# Power.net
KiCad netlist of a schematic drawn in Altium Designer
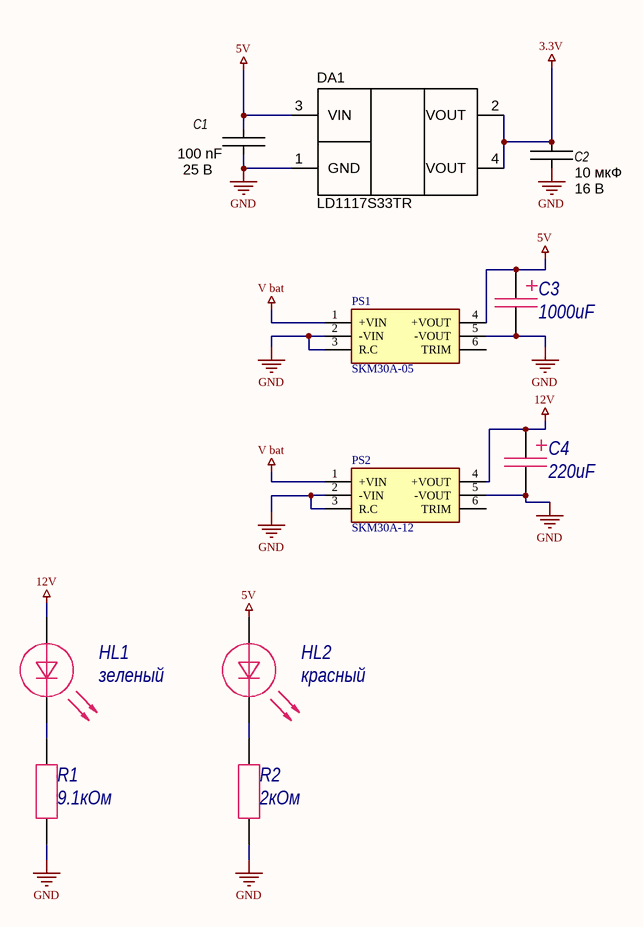
[diagram p0: Power.SchDoc]

(export (version "E")
  (design (tool "Eeschema 10.0.6"))
  (components
    (comp (ref "C1")
      (value "100 nF")
      (footprint "C0402C")
      (description "SMD 0603 ; X7R; 0,01 мкФ; 25 В")
      (fields
        (field (name "PART NUMBER") "CL05B103KA5NNNC")
        (field (name "MANUFACTURER") "SAMSUNG")
        (field (name "VOLTAGE") "25 В")
      )
      (libsource (lib "Capacitors") (part "CL05B103KA5NNNC"))
    )
    (comp (ref "C2")
      (value "10 мкФ")
      (footprint "C0805C")
      (description "SMD 0805; X7R; 10 мкФ; 16 В")
      (fields
        (field (name "PART NUMBER") "CL21B106KOQNNNE")
        (field (name "MANUFACTURER") "SAMSUNG")
        (field (name "VOLTAGE") "16 В")
      )
      (libsource (lib "Capacitors") (part "CL21B106KOQNNNE"))
    )
    (comp (ref "C3")
      (value "1000uF")
      (footprint "Capacitor 8x12")
      (fields (field (name "Comment") "1uF"))
      (libsource (lib "Hydrolib_sch") (part "Capacitor_pol"))
    )
    (comp (ref "C4")
      (value "220uF")
      (footprint "Capacitor 8x12")
      (fields (field (name "Comment") "1uF"))
      (libsource (lib "Hydrolib_sch") (part "Capacitor_pol"))
    )
    (comp (ref "DA1")
      (value "LD1117S33TR")
      (footprint "SOT-223")
      (description "Linear regulator, 3V3")
      (fields (field (name "MANUFACTURER") "STMicroelectronics") (field (name "PART NUMBER") "LD1117S33TR"))
      (libsource (lib "IC") (part "LD1117S33TR"))
    )
    (comp (ref "HL1")
      (value "~")
      (footprint "0805D")
      (fields (field (name "COLOR") "зеленый"))
      (libsource (lib "Hydrolib_sch") (part "LED"))
    )
    (comp (ref "HL2")
      (value "~")
      (footprint "0805D")
      (fields (field (name "COLOR") "красный"))
      (libsource (lib "Hydrolib_sch") (part "LED"))
    )
    (comp (ref "PS1")
      (value "SKM30A-05")
      (footprint "SKM30A05")
      (description "Power Supply")
      (fields (field (name "MOUSER PART NUMBER") "709-SKM30A-05"))
      (libsource (lib "SamacSys") (part "SKM30A-05"))
    )
    (comp (ref "PS2")
      (value "SKM30A-12")
      (footprint "SKM30B12")
      (description "Power Supply")
      (fields (field (name "MOUSER PART NUMBER") "709-SKM30A-12"))
      (libsource (lib "SamacSys") (part "SKM30A-12"))
    )
    (comp (ref "R1")
      (value "9.1кОм")
      (footprint "0805R")
      (fields (field (name "Comment") "Resistor"))
      (libsource (lib "Hydrolib_sch") (part "Resistor"))
    )
    (comp (ref "R2")
      (value "2кОм")
      (footprint "0805R")
      (fields (field (name "Comment") "Resistor"))
      (libsource (lib "Hydrolib_sch") (part "Resistor"))
    )
  )
  (nets
    (net (code "1") (name "3.3V") (class "Default")
      (node (ref "C2") (pin "1") (pinfunction "1_1") (pintype "passive"))
      (node (ref "DA1") (pin "2") (pinfunction "VOUT_2") (pintype "passive"))
      (node (ref "DA1") (pin "4") (pinfunction "VOUT_4") (pintype "passive"))
    )
    (net (code "2") (name "5V") (class "Default")
      (node (ref "C1") (pin "1") (pinfunction "1_1") (pintype "passive"))
      (node (ref "C3") (pin "1") (pinfunction "1_1") (pintype "passive"))
      (node (ref "DA1") (pin "3") (pinfunction "VIN_3") (pintype "passive"))
      (node (ref "HL2") (pin "1") (pinfunction "1_1") (pintype "passive"))
      (node (ref "PS1") (pin "4") (pinfunction "+VOUT_4") (pintype "passive"))
    )
    (net (code "3") (name "12V") (class "Default")
      (node (ref "C4") (pin "1") (pinfunction "1_1") (pintype "passive"))
      (node (ref "HL1") (pin "1") (pinfunction "1_1") (pintype "passive"))
      (node (ref "PS2") (pin "4") (pinfunction "+VOUT_4") (pintype "passive"))
    )
    (net (code "4") (name "GND") (class "Default")
      (node (ref "C1") (pin "2") (pinfunction "2_2") (pintype "passive"))
      (node (ref "C2") (pin "2") (pinfunction "2_2") (pintype "passive"))
      (node (ref "C3") (pin "2") (pinfunction "2_2") (pintype "passive"))
      (node (ref "C4") (pin "2") (pinfunction "2_2") (pintype "passive"))
      (node (ref "DA1") (pin "1") (pinfunction "GND_1") (pintype "passive"))
      (node (ref "PS1") (pin "2") (pinfunction "-VIN_2") (pintype "passive"))
      (node (ref "PS1") (pin "3") (pinfunction "R.C_3") (pintype "passive"))
      (node (ref "PS1") (pin "5") (pinfunction "-VOUT_5") (pintype "passive"))
      (node (ref "PS2") (pin "2") (pinfunction "-VIN_2") (pintype "passive"))
      (node (ref "PS2") (pin "3") (pinfunction "R.C_3") (pintype "passive"))
      (node (ref "PS2") (pin "5") (pinfunction "-VOUT_5") (pintype "passive"))
      (node (ref "R1") (pin "1") (pinfunction "1_1") (pintype "passive"))
      (node (ref "R2") (pin "1") (pinfunction "1_1") (pintype "passive"))
    )
    (net (code "5") (name "Net-(HL1-Pad2)") (class "Default")
      (node (ref "HL1") (pin "2") (pinfunction "2_2") (pintype "passive"))
      (node (ref "R1") (pin "2") (pinfunction "2_2") (pintype "passive"))
    )
    (net (code "6") (name "Net-(HL2-Pad2)") (class "Default")
      (node (ref "HL2") (pin "2") (pinfunction "2_2") (pintype "passive"))
      (node (ref "R2") (pin "2") (pinfunction "2_2") (pintype "passive"))
    )
    (net (code "7") (name "V bat") (class "Default")
      (node (ref "PS1") (pin "1") (pinfunction "+VIN_1") (pintype "passive"))
      (node (ref "PS2") (pin "1") (pinfunction "+VIN_1") (pintype "passive"))
    )
    (net (code "8") (name "unconnected-(PS1-TRIM-Pad6)") (class "Default")
      (node (ref "PS1") (pin "6") (pinfunction "TRIM_6") (pintype "passive"))
    )
    (net (code "9") (name "unconnected-(PS2-TRIM-Pad6)") (class "Default")
      (node (ref "PS2") (pin "6") (pinfunction "TRIM_6") (pintype "passive"))
    )
  )
)
